# MDBU017A.net
KiCad netlist of a schematic drawn in Altium Designer
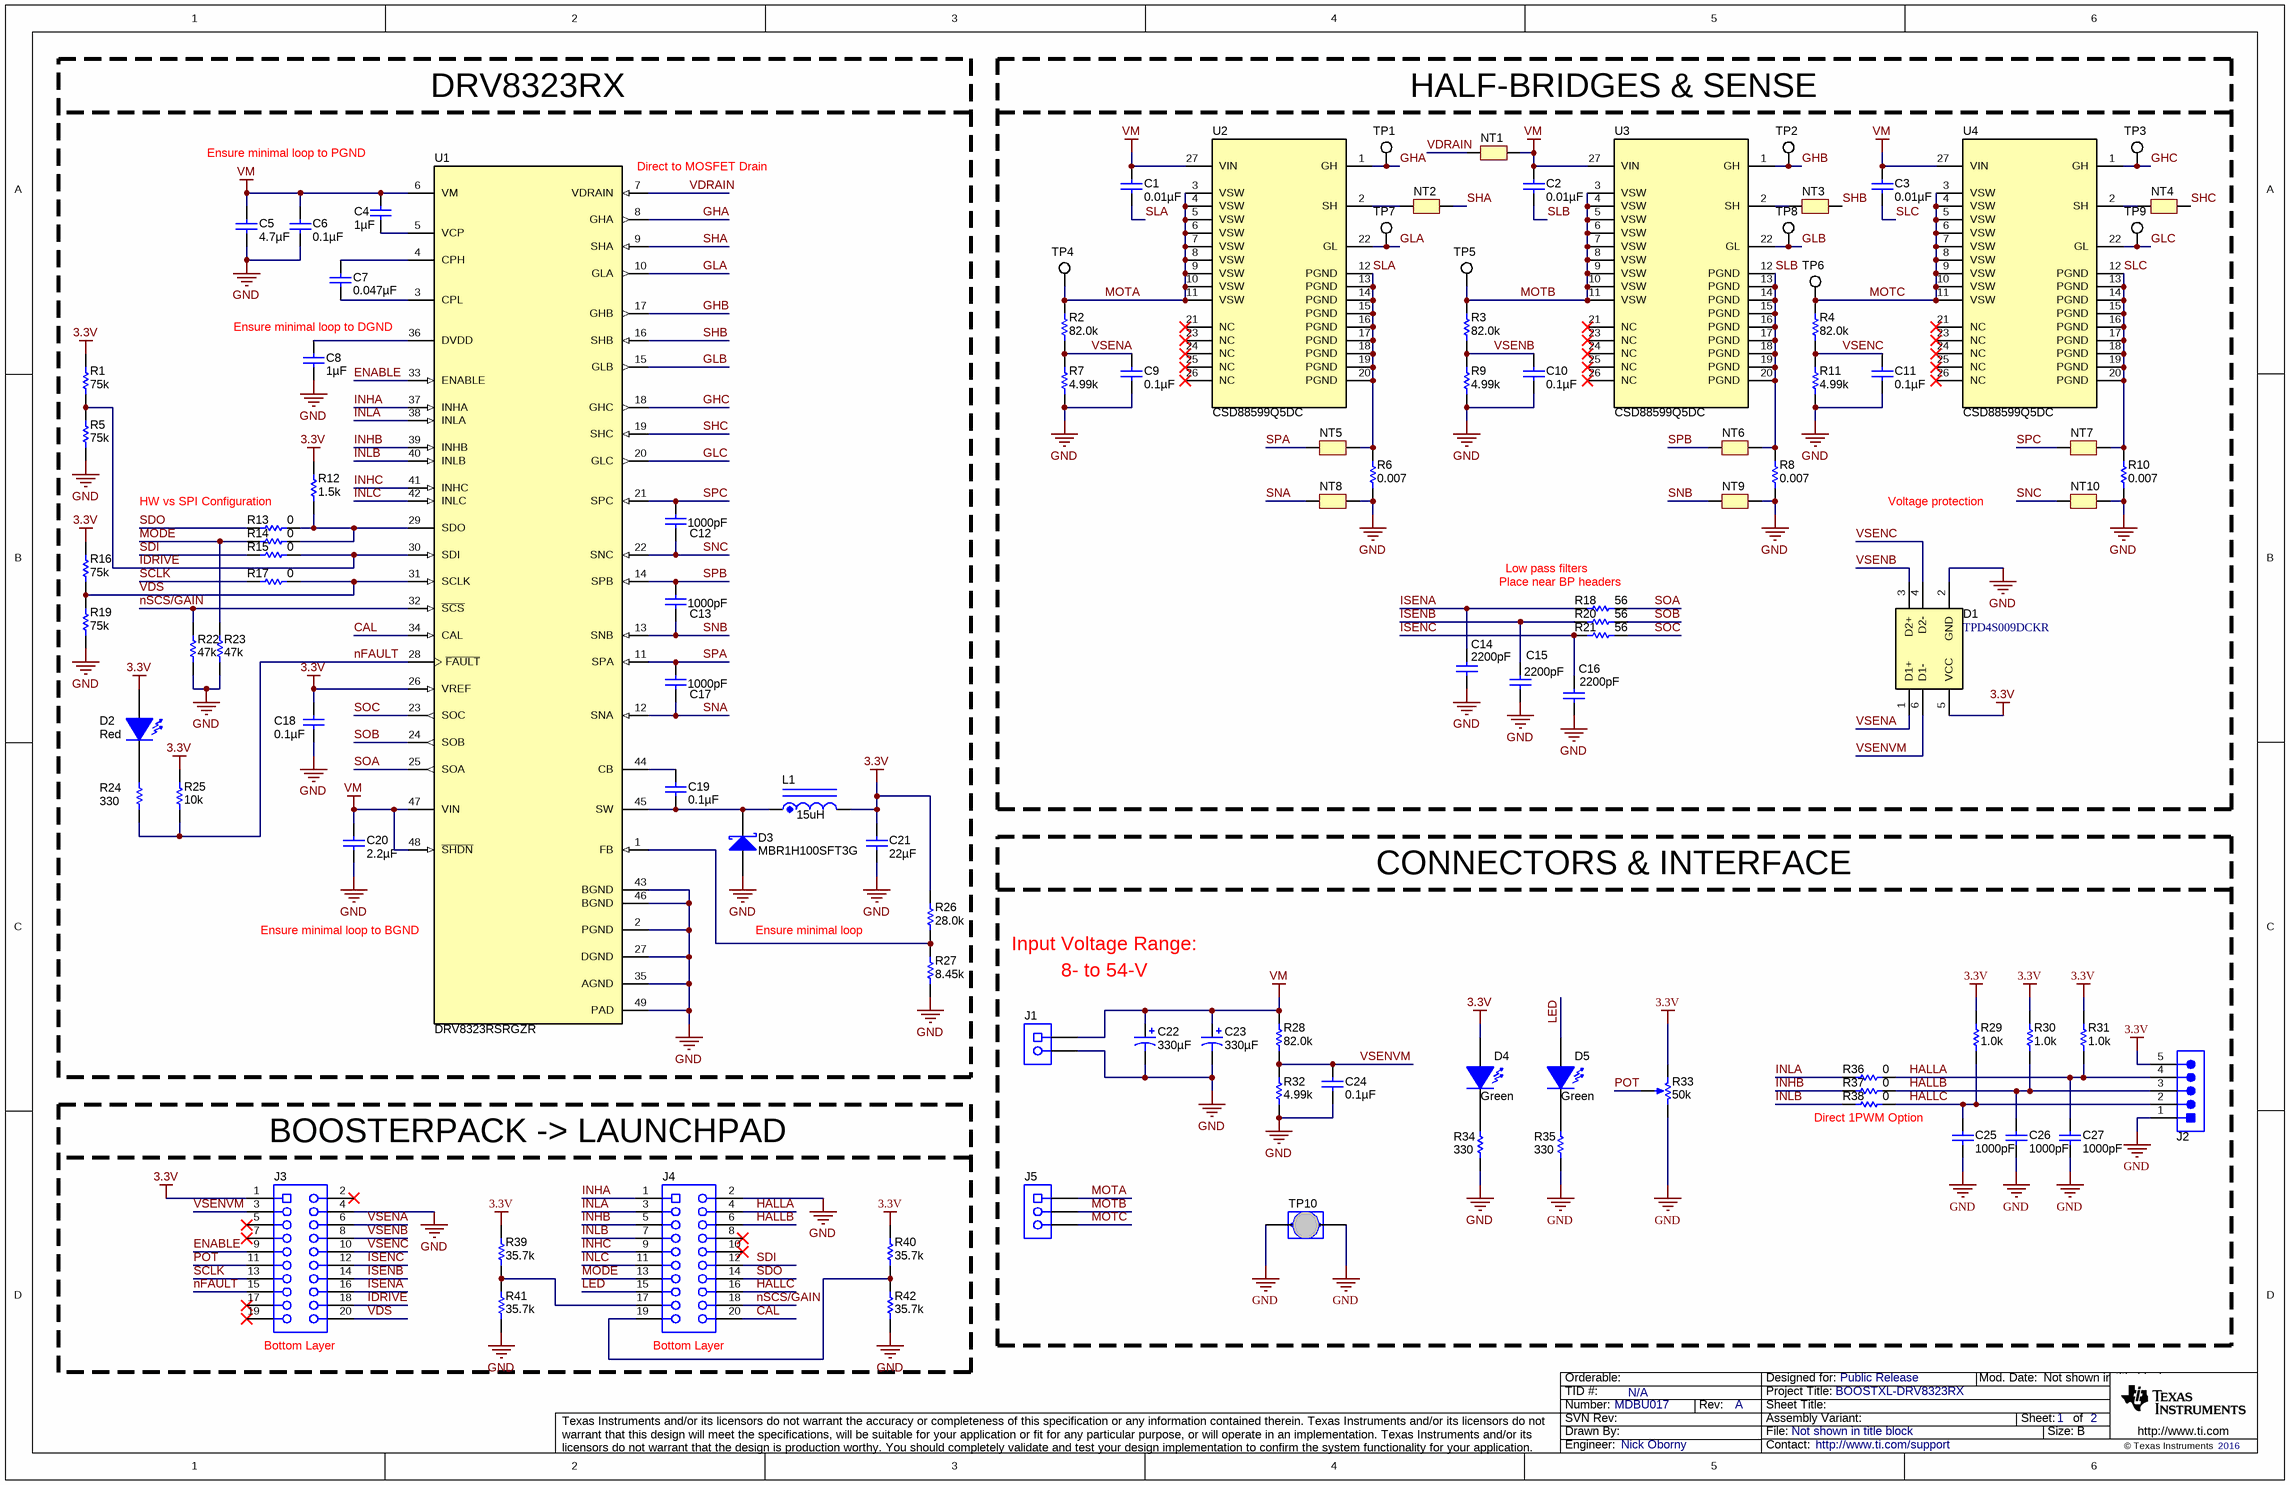
[diagram p0: MDBU017A.SchDoc]

(export (version "E")
  (design (tool "Eeschema 10.0.6"))
  (components
    (comp (ref "C1")
      (value "C0603C103K1RACTU")
      (footprint "0603L")
      (description "CAP, CERM, 0.01 µF, 100 V, +/- 10%, X7R, 0603")
      (fields
        (field (name "VALUEDISPLAYED") "0.01µF")
        (field (name "MANUFACTURER") "Kemet")
        (field (name "PUBLISHER") "Texas Instruments")
      )
      (libsource (lib "Capacitor_Ceramic") (part "C0603C103K1RACTU"))
    )
    (comp (ref "C2")
      (value "C0603C103K1RACTU")
      (footprint "0603L")
      (description "CAP, CERM, 0.01 µF, 100 V, +/- 10%, X7R, 0603")
      (fields
        (field (name "VALUEDISPLAYED") "0.01µF")
        (field (name "MANUFACTURER") "Kemet")
        (field (name "PUBLISHER") "Texas Instruments")
      )
      (libsource (lib "Capacitor_Ceramic") (part "C0603C103K1RACTU"))
    )
    (comp (ref "C3")
      (value "C0603C103K1RACTU")
      (footprint "0603L")
      (description "CAP, CERM, 0.01 µF, 100 V, +/- 10%, X7R, 0603")
      (fields
        (field (name "VALUEDISPLAYED") "0.01µF")
        (field (name "MANUFACTURER") "Kemet")
        (field (name "PUBLISHER") "Texas Instruments")
      )
      (libsource (lib "Capacitor_Ceramic") (part "C0603C103K1RACTU"))
    )
    (comp (ref "C4")
      (value "885012206052")
      (footprint "0603L")
      (description "CAP, CERM, 1 µF, 16 V, +/- 10%, X7R, 0603")
      (fields
        (field (name "VALUEDISPLAYED") "1µF")
        (field (name "MANUFACTURER") "Wurth Elektronik")
        (field (name "PUBLISHER") "Texas Instruments")
      )
      (libsource (lib "Capacitor_Ceramic") (part "885012206052"))
    )
    (comp (ref "C5")
      (value "GRM32ER71K475KE14L")
      (footprint "1210_270L")
      (description "CAP, CERM, 4.7 µF, 80 V, +/- 10%, X7R, 1210")
      (fields
        (field (name "VALUEDISPLAYED") "4.7µF")
        (field (name "MANUFACTURER") "MuRata")
        (field (name "PUBLISHER") "Texas Instruments")
      )
      (libsource (lib "Capacitor_Ceramic") (part "GRM32ER71K475KE14L"))
    )
    (comp (ref "C6")
      (value "GRM188R72A104KA35D")
      (footprint "0603L")
      (description "CAP, CERM, 0.1 µF, 100 V, +/- 10%, X7R, 0603")
      (fields
        (field (name "VALUEDISPLAYED") "0.1µF")
        (field (name "MANUFACTURER") "MuRata")
        (field (name "PUBLISHER") "Texas Instruments")
      )
      (libsource (lib "Capacitor_Ceramic") (part "GRM188R72A104KA35D"))
    )
    (comp (ref "C7")
      (value "C1608X7S2A473K080AB")
      (footprint "0603L")
      (description "CAP, CERM, 0.047 µF, 100 V, +/- 10%, X7S, 0603")
      (fields
        (field (name "VALUEDISPLAYED") "0.047µF")
        (field (name "MANUFACTURER") "TDK")
        (field (name "PUBLISHER") "Texas Instruments")
      )
      (libsource (lib "Capacitor_Ceramic") (part "C1608X7S2A473K080AB"))
    )
    (comp (ref "C8")
      (value "GRM188R70J105KA01D")
      (footprint "0603L")
      (description "CAP, CERM, 1 µF, 6.3 V, +/- 10%, X7R, 0603")
      (fields
        (field (name "VALUEDISPLAYED") "1µF")
        (field (name "MANUFACTURER") "MuRata")
        (field (name "PUBLISHER") "Texas Instruments")
      )
      (libsource (lib "Capacitor_Ceramic") (part "GRM188R70J105KA01D"))
    )
    (comp (ref "C9")
      (value "C0603C104J4RACTU")
      (footprint "0603L")
      (description "CAP, CERM, 0.1 µF, 16 V, +/- 5%, X7R, 0603")
      (fields
        (field (name "VALUEDISPLAYED") "0.1µF")
        (field (name "MANUFACTURER") "Kemet")
        (field (name "PUBLISHER") "Texas Instruments")
      )
      (libsource (lib "Capacitor_Ceramic") (part "C0603C104J4RACTU"))
    )
    (comp (ref "C10")
      (value "C0603C104J4RACTU")
      (footprint "0603L")
      (description "CAP, CERM, 0.1 µF, 16 V, +/- 5%, X7R, 0603")
      (fields
        (field (name "VALUEDISPLAYED") "0.1µF")
        (field (name "MANUFACTURER") "Kemet")
        (field (name "PUBLISHER") "Texas Instruments")
      )
      (libsource (lib "Capacitor_Ceramic") (part "C0603C104J4RACTU"))
    )
    (comp (ref "C11")
      (value "C0603C104J4RACTU")
      (footprint "0603L")
      (description "CAP, CERM, 0.1 µF, 16 V, +/- 5%, X7R, 0603")
      (fields
        (field (name "VALUEDISPLAYED") "0.1µF")
        (field (name "MANUFACTURER") "Kemet")
        (field (name "PUBLISHER") "Texas Instruments")
      )
      (libsource (lib "Capacitor_Ceramic") (part "C0603C104J4RACTU"))
    )
    (comp (ref "C12")
      (value "GRM188R71C102KA01D")
      (footprint "0603L")
      (description "CAP, CERM, 1000pF, 16V, +/-10%, X7R, 0603")
      (fields
        (field (name "VALUEDISPLAYED") "1000pF")
        (field (name "MANUFACTURER") "MuRata")
        (field (name "PUBLISHER") "Texas Instruments")
      )
      (libsource (lib "Capacitor_Ceramic") (part "GRM188R71C102KA01D"))
    )
    (comp (ref "C13")
      (value "GRM188R71C102KA01D")
      (footprint "0603L")
      (description "CAP, CERM, 1000pF, 16V, +/-10%, X7R, 0603")
      (fields
        (field (name "VALUEDISPLAYED") "1000pF")
        (field (name "MANUFACTURER") "MuRata")
        (field (name "PUBLISHER") "Texas Instruments")
      )
      (libsource (lib "Capacitor_Ceramic") (part "GRM188R71C102KA01D"))
    )
    (comp (ref "C14")
      (value "GRM188R71C222KA01D")
      (footprint "0603L")
      (description "CAP, CERM, 2200pF, 16V, +/-10%, X7R, 0603")
      (fields
        (field (name "VALUEDISPLAYED") "2200pF")
        (field (name "MANUFACTURER") "MuRata")
        (field (name "PUBLISHER") "Texas Instruments")
      )
      (libsource (lib "Capacitor_Ceramic") (part "GRM188R71C222KA01D"))
    )
    (comp (ref "C15")
      (value "GRM188R71C222KA01D")
      (footprint "0603L")
      (description "CAP, CERM, 2200pF, 16V, +/-10%, X7R, 0603")
      (fields
        (field (name "VALUEDISPLAYED") "2200pF")
        (field (name "MANUFACTURER") "MuRata")
        (field (name "PUBLISHER") "Texas Instruments")
      )
      (libsource (lib "Capacitor_Ceramic") (part "GRM188R71C222KA01D"))
    )
    (comp (ref "C16")
      (value "GRM188R71C222KA01D")
      (footprint "0603L")
      (description "CAP, CERM, 2200pF, 16V, +/-10%, X7R, 0603")
      (fields
        (field (name "VALUEDISPLAYED") "2200pF")
        (field (name "MANUFACTURER") "MuRata")
        (field (name "PUBLISHER") "Texas Instruments")
      )
      (libsource (lib "Capacitor_Ceramic") (part "GRM188R71C222KA01D"))
    )
    (comp (ref "C17")
      (value "GRM188R71C102KA01D")
      (footprint "0603L")
      (description "CAP, CERM, 1000pF, 16V, +/-10%, X7R, 0603")
      (fields
        (field (name "VALUEDISPLAYED") "1000pF")
        (field (name "MANUFACTURER") "MuRata")
        (field (name "PUBLISHER") "Texas Instruments")
      )
      (libsource (lib "Capacitor_Ceramic") (part "GRM188R71C102KA01D"))
    )
    (comp (ref "C18")
      (value "GRM188R70J104KA01D")
      (footprint "0603L")
      (description "CAP, CERM, 0.1 µF, 6.3 V, +/- 10%, X7R, 0603")
      (fields
        (field (name "VALUEDISPLAYED") "0.1µF")
        (field (name "MANUFACTURER") "MuRata")
        (field (name "PUBLISHER") "Texas Instruments")
      )
      (libsource (lib "Capacitor_Ceramic") (part "GRM188R70J104KA01D"))
    )
    (comp (ref "C19")
      (value "0603YC104JAT2A")
      (footprint "0603L")
      (description "CAP, CERM, 0.1 µF, 16 V, +/- 5%, X7R, 0603")
      (fields
        (field (name "VALUEDISPLAYED") "0.1µF")
        (field (name "MANUFACTURER") "AVX")
        (field (name "PUBLISHER") "Texas Instruments")
      )
      (libsource (lib "Capacitor_Ceramic") (part "0603YC104JAT2A"))
    )
    (comp (ref "C20")
      (value "HMK325B7225KN-T")
      (footprint "1210L")
      (description "CAP, CERM, 2.2 µF, 100 V, +/- 10%, X7R, 1210")
      (fields
        (field (name "VALUEDISPLAYED") "2.2µF")
        (field (name "MANUFACTURER") "Taiyo Yuden")
        (field (name "PUBLISHER") "Texas Instruments")
      )
      (libsource (lib "Capacitor_Ceramic") (part "HMK325B7225KN-T"))
    )
    (comp (ref "C21")
      (value "C3216X7S1A226M160AC")
      (footprint "1206_180L")
      (description "CAP, CERM, 22 µF, 10 V, +/- 20%, X7S, 1206")
      (fields
        (field (name "VALUEDISPLAYED") "22µF")
        (field (name "MANUFACTURER") "TDK")
        (field (name "PUBLISHER") "Texas Instruments")
      )
      (libsource (lib "Capacitor_Ceramic") (part "C3216X7S1A226M160AC"))
    )
    (comp (ref "C22")
      (value "EMVA630ADA331MKG5S")
      (footprint "CAPSMT_62_KG5")
      (description "CAP, AL, 330 µF, 63 V, +/- 20%, SMD")
      (fields
        (field (name "VALUEDISPLAYED") "330µF")
        (field (name "MANUFACTURER") "Chemi-Con")
        (field (name "PUBLISHER") "Texas Instruments")
      )
      (libsource (lib "Capacitor_Aluminum") (part "EMVA630ADA331MKG5S"))
    )
    (comp (ref "C23")
      (value "EMVA630ADA331MKG5S")
      (footprint "CAPSMT_62_KG5")
      (description "CAP, AL, 330 µF, 63 V, +/- 20%, SMD")
      (fields
        (field (name "VALUEDISPLAYED") "330µF")
        (field (name "MANUFACTURER") "Chemi-Con")
        (field (name "PUBLISHER") "Texas Instruments")
      )
      (libsource (lib "Capacitor_Aluminum") (part "EMVA630ADA331MKG5S"))
    )
    (comp (ref "C24")
      (value "C0603C104J4RACTU")
      (footprint "0603L")
      (description "CAP, CERM, 0.1 µF, 16 V, +/- 5%, X7R, 0603")
      (fields
        (field (name "VALUEDISPLAYED") "0.1µF")
        (field (name "MANUFACTURER") "Kemet")
        (field (name "PUBLISHER") "Texas Instruments")
      )
      (libsource (lib "Capacitor_Ceramic") (part "C0603C104J4RACTU"))
    )
    (comp (ref "C25")
      (value "885012206034")
      (footprint "0603L")
      (description "CAP, CERM, 1000 pF, 16 V, +/- 10%, X7R, 0603")
      (fields
        (field (name "VALUEDISPLAYED") "1000pF")
        (field (name "MANUFACTURER") "Wurth Elektronik")
        (field (name "PUBLISHER") "Texas Instruments")
      )
      (libsource (lib "Capacitor_Ceramic") (part "885012206034"))
    )
    (comp (ref "C26")
      (value "885012206034")
      (footprint "0603L")
      (description "CAP, CERM, 1000 pF, 16 V, +/- 10%, X7R, 0603")
      (fields
        (field (name "VALUEDISPLAYED") "1000pF")
        (field (name "MANUFACTURER") "Wurth Elektronik")
        (field (name "PUBLISHER") "Texas Instruments")
      )
      (libsource (lib "Capacitor_Ceramic") (part "885012206034"))
    )
    (comp (ref "C27")
      (value "885012206034")
      (footprint "0603L")
      (description "CAP, CERM, 1000 pF, 16 V, +/- 10%, X7R, 0603")
      (fields
        (field (name "VALUEDISPLAYED") "1000pF")
        (field (name "MANUFACTURER") "Wurth Elektronik")
        (field (name "PUBLISHER") "Texas Instruments")
      )
      (libsource (lib "Capacitor_Ceramic") (part "885012206034"))
    )
    (comp (ref "D1")
      (value "TPD4S009DCKR")
      (footprint "DCK0006A_L")
      (fields
        (field (name "MANUFACTURER") "Texas Instruments")
        (field (name "ALTERNATE PARTNUMBER") "Equivalent")
      )
      (libsource (lib "TI Interface ESD EMI Protection") (part "TPD4S009DCKR"))
    )
    (comp (ref "D2")
      (value "Red")
      (footprint "LED_LTST-C170")
      (description "LED, Red, SMD")
      (fields
        (field (name "MANUFACTURER") "Lite-On")
        (field (name "PARTNUMBER") "LTST-C170KRKT")
        (field (name "PUBLISHER") "Texas Instruments")
      )
      (libsource (lib "LED") (part "LTST-C170KRKT"))
    )
    (comp (ref "D3")
      (value "MBR1H100SFT3G")
      (footprint "SOD-123FL")
      (description "Diode, Schottky, 100 V, 1 A, SOD-123FL")
      (fields (field (name "MANUFACTURER") "ON Semiconductor") (field (name "PUBLISHER") "Texas Instruments"))
      (libsource (lib "Diode") (part "MBR1H100SFT3G"))
    )
    (comp (ref "D4")
      (value "Green")
      (footprint "LED_LTST-C171")
      (description "LED, Green, SMD")
      (fields
        (field (name "MANUFACTURER") "Lite-On")
        (field (name "PARTNUMBER") "LTST-C171GKT")
        (field (name "PUBLISHER") "Texas Instruments")
      )
      (libsource (lib "LED") (part "LTST-C171GKT"))
    )
    (comp (ref "D5")
      (value "Green")
      (footprint "LED_LTST-C171")
      (description "LED, Green, SMD")
      (fields
        (field (name "MANUFACTURER") "Lite-On")
        (field (name "PARTNUMBER") "LTST-C171GKT")
        (field (name "PUBLISHER") "Texas Instruments")
      )
      (libsource (lib "LED") (part "LTST-C171GKT"))
    )
    (comp (ref "J1")
      (value "691 101 710 002")
      (footprint "Wurth_691101710002")
      (description "Terminal Block, 5 mm, 2x1, Tin, TH")
      (fields
        (field (name "MANUFACTURER") "Wurth Elektronik eiSos")
        (field (name "SYMBOLCREATOR") "a0412235")
        (field (name "PUBLISHER") "Texas Instruments")
      )
      (libsource (lib "Connectors_Other") (part "691 101 710 002"))
    )
    (comp (ref "J2")
      (value "PEC05SAAN")
      (footprint "Sullins_PxC05SAAN")
      (description "Header, 2.54mm, 5x1, Tin, TH")
      (fields
        (field (name "MANUFACTURER") "Sullins Connector Solutions")
        (field (name "SYMBOLCREATOR") "a0412235")
        (field (name "PUBLISHER") "Texas Instruments")
      )
      (libsource (lib "Connectors_Sullins") (part "PEC05SAAN"))
    )
    (comp (ref "J3")
      (value "SSQ-110-03-G-D")
      (footprint "Samtec_SSQ-110-03-x-D")
      (description "Receptacle, 2.54mm, 10x2, Gold, TH")
      (fields
        (field (name "MANUFACTURER") "Samtec")
        (field (name "SYMBOLCREATOR") "a0412235")
        (field (name "PUBLISHER") "Texas Instruments")
      )
      (libsource (lib "Connectors_Samtec") (part "SSQ-110-03-G-D"))
    )
    (comp (ref "J4")
      (value "SSQ-110-03-G-D")
      (footprint "Samtec_SSQ-110-03-x-D")
      (description "Receptacle, 2.54mm, 10x2, Gold, TH")
      (fields
        (field (name "MANUFACTURER") "Samtec")
        (field (name "SYMBOLCREATOR") "a0412235")
        (field (name "PUBLISHER") "Texas Instruments")
      )
      (libsource (lib "Connectors_Samtec") (part "SSQ-110-03-G-D"))
    )
    (comp (ref "J5")
      (value "691 101 710 003")
      (footprint "Wurth_691101710003")
      (description "Terminal Block, 5 mm, 3x1, Tin, TH")
      (fields
        (field (name "MANUFACTURER") "Wurth Elektronik eiSos")
        (field (name "SYMBOLCREATOR") "a0412235")
        (field (name "PUBLISHER") "Texas Instruments")
      )
      (libsource (lib "Connectors_Other") (part "691 101 710 003"))
    )
    (comp (ref "L1")
      (value "15uH")
      (footprint "SD53")
      (description "Inductor, Shielded Drum Core, Ferrite, 15 µH, 1.1 A, 0.122 ohm, SMD")
      (fields
        (field (name "PARTNUMBER") "SD53-150-R")
        (field (name "MANUFACTURER") "Cooper Bussman")
        (field (name "SYMBOLCREATOR") "a0412235")
        (field (name "PUBLISHER") "Texas Instruments")
      )
      (libsource (lib "Inductor_Other") (part "SD53-150-R"))
    )
    (comp (ref "NT1")
      (value "Net-Tie")
      (footprint "Net-Tie_10mil")
      (description "Single point connection between nets.")
      (fields (field (name "SYMBOLCREATOR") "codlsc") (field (name "PUBLISHER") "Texas Instruments"))
      (libsource (lib "MiscParts") (part "Net-Tie"))
    )
    (comp (ref "NT2")
      (value "Net-Tie")
      (footprint "Net-Tie_10mil")
      (description "Single point connection between nets.")
      (fields (field (name "SYMBOLCREATOR") "codlsc") (field (name "PUBLISHER") "Texas Instruments"))
      (libsource (lib "MiscParts") (part "Net-Tie"))
    )
    (comp (ref "NT3")
      (value "Net-Tie")
      (footprint "Net-Tie_10mil")
      (description "Single point connection between nets.")
      (fields (field (name "SYMBOLCREATOR") "codlsc") (field (name "PUBLISHER") "Texas Instruments"))
      (libsource (lib "MiscParts") (part "Net-Tie"))
    )
    (comp (ref "NT4")
      (value "Net-Tie")
      (footprint "Net-Tie_10mil")
      (description "Single point connection between nets.")
      (fields (field (name "SYMBOLCREATOR") "codlsc") (field (name "PUBLISHER") "Texas Instruments"))
      (libsource (lib "MiscParts") (part "Net-Tie"))
    )
    (comp (ref "NT5")
      (value "Net-Tie")
      (footprint "Net-Tie_10mil")
      (description "Single point connection between nets.")
      (fields (field (name "SYMBOLCREATOR") "codlsc") (field (name "PUBLISHER") "Texas Instruments"))
      (libsource (lib "MiscParts") (part "Net-Tie"))
    )
    (comp (ref "NT6")
      (value "Net-Tie")
      (footprint "Net-Tie_10mil")
      (description "Single point connection between nets.")
      (fields (field (name "SYMBOLCREATOR") "codlsc") (field (name "PUBLISHER") "Texas Instruments"))
      (libsource (lib "MiscParts") (part "Net-Tie"))
    )
    (comp (ref "NT7")
      (value "Net-Tie")
      (footprint "Net-Tie_10mil")
      (description "Single point connection between nets.")
      (fields (field (name "SYMBOLCREATOR") "codlsc") (field (name "PUBLISHER") "Texas Instruments"))
      (libsource (lib "MiscParts") (part "Net-Tie"))
    )
    (comp (ref "NT8")
      (value "Net-Tie")
      (footprint "Net-Tie_10mil")
      (description "Single point connection between nets.")
      (fields (field (name "SYMBOLCREATOR") "codlsc") (field (name "PUBLISHER") "Texas Instruments"))
      (libsource (lib "MiscParts") (part "Net-Tie"))
    )
    (comp (ref "NT9")
      (value "Net-Tie")
      (footprint "Net-Tie_10mil")
      (description "Single point connection between nets.")
      (fields (field (name "SYMBOLCREATOR") "codlsc") (field (name "PUBLISHER") "Texas Instruments"))
      (libsource (lib "MiscParts") (part "Net-Tie"))
    )
    (comp (ref "NT10")
      (value "Net-Tie")
      (footprint "Net-Tie_10mil")
      (description "Single point connection between nets.")
      (fields (field (name "SYMBOLCREATOR") "codlsc") (field (name "PUBLISHER") "Texas Instruments"))
      (libsource (lib "MiscParts") (part "Net-Tie"))
    )
    (comp (ref "R1")
      (value "CRCW060375K0JNEA")
      (footprint "0603L")
      (description "RES, 75 k, 5%, 0.1 W, 0603")
      (fields
        (field (name "VALUEDISPLAYED") "75k")
        (field (name "MANUFACTURER") "Vishay-Dale")
        (field (name "PUBLISHER") "Texas Instruments")
      )
      (libsource (lib "Resistor_0603") (part "CRCW060375K0JNEA"))
    )
    (comp (ref "R2")
      (value "RC0603FR-0782KL")
      (footprint "0603L")
      (description "RES, 82.0 k, 1%, 0.1 W, 0603")
      (fields
        (field (name "VALUEDISPLAYED") "82.0k")
        (field (name "MANUFACTURER") "Yageo America")
        (field (name "PUBLISHER") "Texas Instruments")
      )
      (libsource (lib "Resistor_0603") (part "RC0603FR-0782KL"))
    )
    (comp (ref "R3")
      (value "RC0603FR-0782KL")
      (footprint "0603L")
      (description "RES, 82.0 k, 1%, 0.1 W, 0603")
      (fields
        (field (name "VALUEDISPLAYED") "82.0k")
        (field (name "MANUFACTURER") "Yageo America")
        (field (name "PUBLISHER") "Texas Instruments")
      )
      (libsource (lib "Resistor_0603") (part "RC0603FR-0782KL"))
    )
    (comp (ref "R4")
      (value "RC0603FR-0782KL")
      (footprint "0603L")
      (description "RES, 82.0 k, 1%, 0.1 W, 0603")
      (fields
        (field (name "VALUEDISPLAYED") "82.0k")
        (field (name "MANUFACTURER") "Yageo America")
        (field (name "PUBLISHER") "Texas Instruments")
      )
      (libsource (lib "Resistor_0603") (part "RC0603FR-0782KL"))
    )
    (comp (ref "R5")
      (value "CRCW060375K0JNEA")
      (footprint "0603L")
      (description "RES, 75 k, 5%, 0.1 W, 0603")
      (fields
        (field (name "VALUEDISPLAYED") "75k")
        (field (name "MANUFACTURER") "Vishay-Dale")
        (field (name "PUBLISHER") "Texas Instruments")
      )
      (libsource (lib "Resistor_0603") (part "CRCW060375K0JNEA"))
    )
    (comp (ref "R6")
      (value "CRE2512-FZ-R007E-3")
      (footprint "2512L")
      (description "RES SMD 0.007 OHM 1% 3W 2512")
      (fields
        (field (name "VALUEDISPLAYED") "0.007")
        (field (name "MANUFACTURER") "Bourns Inc.")
        (field (name "PUBLISHER") "Texas Instruments")
      )
      (libsource (lib "Resistor_2512") (part "PMR100HZPFU7L00"))
    )
    (comp (ref "R7")
      (value "RC0603FR-074K99L")
      (footprint "0603L")
      (description "RES, 4.99 k, 1%, 0.1 W, 0603")
      (fields
        (field (name "VALUEDISPLAYED") "4.99k")
        (field (name "MANUFACTURER") "Yageo America")
        (field (name "PUBLISHER") "Texas Instruments")
      )
      (libsource (lib "Resistor_0603") (part "RC0603FR-074K99L"))
    )
    (comp (ref "R8")
      (value "CRE2512-FZ-R007E-3")
      (footprint "2512L")
      (description "RES SMD 0.007 OHM 1% 3W 2512")
      (fields
        (field (name "VALUEDISPLAYED") "0.007")
        (field (name "MANUFACTURER") "Bourns Inc.")
        (field (name "PUBLISHER") "Texas Instruments")
      )
      (libsource (lib "Resistor_2512") (part "PMR100HZPFU7L00"))
    )
    (comp (ref "R9")
      (value "RC0603FR-074K99L")
      (footprint "0603L")
      (description "RES, 4.99 k, 1%, 0.1 W, 0603")
      (fields
        (field (name "VALUEDISPLAYED") "4.99k")
        (field (name "MANUFACTURER") "Yageo America")
        (field (name "PUBLISHER") "Texas Instruments")
      )
      (libsource (lib "Resistor_0603") (part "RC0603FR-074K99L"))
    )
    (comp (ref "R10")
      (value "CRE2512-FZ-R007E-3")
      (footprint "2512L")
      (description "RES SMD 0.007 OHM 1% 3W 2512")
      (fields
        (field (name "VALUEDISPLAYED") "0.007")
        (field (name "MANUFACTURER") "Bourns Inc.")
        (field (name "PUBLISHER") "Texas Instruments")
      )
      (libsource (lib "Resistor_2512") (part "PMR100HZPFU7L00"))
    )
    (comp (ref "R11")
      (value "RC0603FR-074K99L")
      (footprint "0603L")
      (description "RES, 4.99 k, 1%, 0.1 W, 0603")
      (fields
        (field (name "VALUEDISPLAYED") "4.99k")
        (field (name "MANUFACTURER") "Yageo America")
        (field (name "PUBLISHER") "Texas Instruments")
      )
      (libsource (lib "Resistor_0603") (part "RC0603FR-074K99L"))
    )
    (comp (ref "R12")
      (value "CRCW06031K50JNEA")
      (footprint "0603L")
      (description "RES, 1.5 k, 5%, 0.1 W, 0603")
      (fields
        (field (name "VALUEDISPLAYED") "1.5k")
        (field (name "MANUFACTURER") "Vishay-Dale")
        (field (name "PUBLISHER") "Texas Instruments")
      )
      (libsource (lib "Resistor_0603") (part "CRCW06031K50JNEA"))
    )
    (comp (ref "R13")
      (value "0")
      (footprint "0603L")
      (description "RES, 0, 5%, 0.1 W, 0603")
      (fields
        (field (name "PARTNUMBER") "CRCW06030000Z0EA")
        (field (name "MANUFACTURER") "Vishay-Dale")
        (field (name "PUBLISHER") "Texas Instruments")
      )
      (libsource (lib "Resistor_0603") (part "CRCW06030000Z0EA"))
    )
    (comp (ref "R14")
      (value "0")
      (footprint "0603L")
      (description "RES, 0, 5%, 0.1 W, 0603")
      (fields
        (field (name "PARTNUMBER") "CRCW06030000Z0EA")
        (field (name "MANUFACTURER") "Vishay-Dale")
        (field (name "PUBLISHER") "Texas Instruments")
      )
      (libsource (lib "Resistor_0603") (part "CRCW06030000Z0EA"))
    )
    (comp (ref "R15")
      (value "0")
      (footprint "0603L")
      (description "RES, 0, 5%, 0.1 W, 0603")
      (fields
        (field (name "PARTNUMBER") "CRCW06030000Z0EA")
        (field (name "MANUFACTURER") "Vishay-Dale")
        (field (name "PUBLISHER") "Texas Instruments")
      )
      (libsource (lib "Resistor_0603") (part "CRCW06030000Z0EA"))
    )
    (comp (ref "R16")
      (value "CRCW060375K0JNEA")
      (footprint "0603L")
      (description "RES, 75 k, 5%, 0.1 W, 0603")
      (fields
        (field (name "VALUEDISPLAYED") "75k")
        (field (name "MANUFACTURER") "Vishay-Dale")
        (field (name "PUBLISHER") "Texas Instruments")
      )
      (libsource (lib "Resistor_0603") (part "CRCW060375K0JNEA"))
    )
    (comp (ref "R17")
      (value "0")
      (footprint "0603L")
      (description "RES, 0, 5%, 0.1 W, 0603")
      (fields
        (field (name "PARTNUMBER") "CRCW06030000Z0EA")
        (field (name "MANUFACTURER") "Vishay-Dale")
        (field (name "PUBLISHER") "Texas Instruments")
      )
      (libsource (lib "Resistor_0603") (part "CRCW06030000Z0EA"))
    )
    (comp (ref "R18")
      (value "56")
      (footprint "0603L")
      (description "RES, 56 ohm, 5%, 0.1W, 0603")
      (fields
        (field (name "PARTNUMBER") "CRCW060356R0JNEA")
        (field (name "MANUFACTURER") "Vishay-Dale")
        (field (name "PUBLISHER") "Texas Instruments")
      )
      (libsource (lib "Resistor_0603") (part "CRCW060356R0JNEA"))
    )
    (comp (ref "R19")
      (value "CRCW060375K0JNEA")
      (footprint "0603L")
      (description "RES, 75 k, 5%, 0.1 W, 0603")
      (fields
        (field (name "VALUEDISPLAYED") "75k")
        (field (name "MANUFACTURER") "Vishay-Dale")
        (field (name "PUBLISHER") "Texas Instruments")
      )
      (libsource (lib "Resistor_0603") (part "CRCW060375K0JNEA"))
    )
    (comp (ref "R20")
      (value "56")
      (footprint "0603L")
      (description "RES, 56 ohm, 5%, 0.1W, 0603")
      (fields
        (field (name "PARTNUMBER") "CRCW060356R0JNEA")
        (field (name "MANUFACTURER") "Vishay-Dale")
        (field (name "PUBLISHER") "Texas Instruments")
      )
      (libsource (lib "Resistor_0603") (part "CRCW060356R0JNEA"))
    )
    (comp (ref "R21")
      (value "56")
      (footprint "0603L")
      (description "RES, 56 ohm, 5%, 0.1W, 0603")
      (fields
        (field (name "PARTNUMBER") "CRCW060356R0JNEA")
        (field (name "MANUFACTURER") "Vishay-Dale")
        (field (name "PUBLISHER") "Texas Instruments")
      )
      (libsource (lib "Resistor_0603") (part "CRCW060356R0JNEA"))
    )
    (comp (ref "R22")
      (value "CRCW060347K0JNEA")
      (footprint "0603L")
      (description "RES, 47 k, 5%, 0.1 W, 0603")
      (fields
        (field (name "VALUEDISPLAYED") "47k")
        (field (name "MANUFACTURER") "Vishay-Dale")
        (field (name "PUBLISHER") "Texas Instruments")
      )
      (libsource (lib "Resistor_0603") (part "CRCW060347K0JNEA"))
    )
    (comp (ref "R23")
      (value "CRCW060347K0JNEA")
      (footprint "0603L")
      (description "RES, 47 k, 5%, 0.1 W, 0603")
      (fields
        (field (name "VALUEDISPLAYED") "47k")
        (field (name "MANUFACTURER") "Vishay-Dale")
        (field (name "PUBLISHER") "Texas Instruments")
      )
      (libsource (lib "Resistor_0603") (part "CRCW060347K0JNEA"))
    )
    (comp (ref "R24")
      (value "330")
      (footprint "0603L")
      (description "RES, 330 ohm, 5%, 0.1W, 0603")
      (fields
        (field (name "PARTNUMBER") "CRCW0603330RJNEA")
        (field (name "MANUFACTURER") "Vishay-Dale")
        (field (name "PUBLISHER") "Texas Instruments")
      )
      (libsource (lib "Resistor_0603") (part "CRCW0603330RJNEA"))
    )
    (comp (ref "R25")
      (value "CRCW060310K0JNEA")
      (footprint "0603L")
      (description "RES, 10 k, 5%, 0.1 W, 0603")
      (fields
        (field (name "VALUEDISPLAYED") "10k")
        (field (name "MANUFACTURER") "Vishay-Dale")
        (field (name "PUBLISHER") "Texas Instruments")
      )
      (libsource (lib "Resistor_0603") (part "CRCW060310K0JNEA"))
    )
    (comp (ref "R26")
      (value "CRCW060328K0FKEA")
      (footprint "0603L")
      (description "RES, 28.0 k, 1%, 0.1 W, 0603")
      (fields
        (field (name "VALUEDISPLAYED") "28.0k")
        (field (name "MANUFACTURER") "Vishay-Dale")
        (field (name "PUBLISHER") "Texas Instruments")
      )
      (libsource (lib "Resistor_0603") (part "CRCW060328K0FKEA"))
    )
    (comp (ref "R27")
      (value "CRCW06038K45FKEA")
      (footprint "0603L")
      (description "RES, 8.45 k, 1%, 0.1 W, 0603")
      (fields
        (field (name "VALUEDISPLAYED") "8.45k")
        (field (name "MANUFACTURER") "Vishay-Dale")
        (field (name "PUBLISHER") "Texas Instruments")
      )
      (libsource (lib "Resistor_0603") (part "CRCW06038K45FKEA"))
    )
    (comp (ref "R28")
      (value "RC0603FR-0782KL")
      (footprint "0603L")
      (description "RES, 82.0 k, 1%, 0.1 W, 0603")
      (fields
        (field (name "VALUEDISPLAYED") "82.0k")
        (field (name "MANUFACTURER") "Yageo America")
        (field (name "PUBLISHER") "Texas Instruments")
      )
      (libsource (lib "Resistor_0603") (part "RC0603FR-0782KL"))
    )
    (comp (ref "R29")
      (value "CRCW06031K00JNEA")
      (footprint "0603L")
      (description "RES, 1.0 k, 5%, 0.1 W, 0603")
      (fields
        (field (name "VALUEDISPLAYED") "1.0k")
        (field (name "MANUFACTURER") "Vishay-Dale")
        (field (name "PUBLISHER") "Texas Instruments")
      )
      (libsource (lib "Resistor_0603") (part "CRCW06031K00JNEA"))
    )
    (comp (ref "R30")
      (value "CRCW06031K00JNEA")
      (footprint "0603L")
      (description "RES, 1.0 k, 5%, 0.1 W, 0603")
      (fields
        (field (name "VALUEDISPLAYED") "1.0k")
        (field (name "MANUFACTURER") "Vishay-Dale")
        (field (name "PUBLISHER") "Texas Instruments")
      )
      (libsource (lib "Resistor_0603") (part "CRCW06031K00JNEA"))
    )
    (comp (ref "R31")
      (value "CRCW06031K00JNEA")
      (footprint "0603L")
      (description "RES, 1.0 k, 5%, 0.1 W, 0603")
      (fields
        (field (name "VALUEDISPLAYED") "1.0k")
        (field (name "MANUFACTURER") "Vishay-Dale")
        (field (name "PUBLISHER") "Texas Instruments")
      )
      (libsource (lib "Resistor_0603") (part "CRCW06031K00JNEA"))
    )
    (comp (ref "R32")
      (value "RC0603FR-074K99L")
      (footprint "0603L")
      (description "RES, 4.99 k, 1%, 0.1 W, 0603")
      (fields
        (field (name "VALUEDISPLAYED") "4.99k")
        (field (name "MANUFACTURER") "Yageo America")
        (field (name "PUBLISHER") "Texas Instruments")
      )
      (libsource (lib "Resistor_0603") (part "RC0603FR-074K99L"))
    )
    (comp (ref "R33")
      (value "50k")
      (footprint "Bourns_3352T")
      (description "Trimming Potentiometer, 50K, 0.5W, TH")
      (fields
        (field (name "PARTNUMBER") "3352T-1-503LF")
        (field (name "MANUFACTURER") "Bourns")
        (field (name "SYMBOLCREATOR") "a0412235")
        (field (name "PUBLISHER") "Texas Instruments")
      )
      (libsource (lib "Other_Passive") (part "3352T-1-503LF"))
    )
    (comp (ref "R34")
      (value "330")
      (footprint "0603L")
      (description "RES, 330 ohm, 5%, 0.1W, 0603")
      (fields
        (field (name "PARTNUMBER") "CRCW0603330RJNEA")
        (field (name "MANUFACTURER") "Vishay-Dale")
        (field (name "PUBLISHER") "Texas Instruments")
      )
      (libsource (lib "Resistor_0603") (part "CRCW0603330RJNEA"))
    )
    (comp (ref "R35")
      (value "330")
      (footprint "0603L")
      (description "RES, 330, 5%, 0.1 W, 0603")
      (fields
        (field (name "PARTNUMBER") "CRCW0603330RJNEA")
        (field (name "MANUFACTURER") "Vishay-Dale")
        (field (name "PUBLISHER") "Texas Instruments")
      )
      (libsource (lib "Resistor_0603") (part "CRCW0603330RJNEA"))
    )
    (comp (ref "R36")
      (value "0")
      (footprint "0603L")
      (description "RES, 0, 5%, 0.1 W, 0603")
      (fields
        (field (name "PARTNUMBER") "CRCW06030000Z0EA")
        (field (name "MANUFACTURER") "Vishay-Dale")
        (field (name "PUBLISHER") "Texas Instruments")
      )
      (libsource (lib "Resistor_0603") (part "CRCW06030000Z0EA"))
    )
    (comp (ref "R37")
      (value "0")
      (footprint "0603L")
      (description "RES, 0, 5%, 0.1 W, 0603")
      (fields
        (field (name "PARTNUMBER") "CRCW06030000Z0EA")
        (field (name "MANUFACTURER") "Vishay-Dale")
        (field (name "PUBLISHER") "Texas Instruments")
      )
      (libsource (lib "Resistor_0603") (part "CRCW06030000Z0EA"))
    )
    (comp (ref "R38")
      (value "0")
      (footprint "0603L")
      (description "RES, 0, 5%, 0.1 W, 0603")
      (fields
        (field (name "PARTNUMBER") "CRCW06030000Z0EA")
        (field (name "MANUFACTURER") "Vishay-Dale")
        (field (name "PUBLISHER") "Texas Instruments")
      )
      (libsource (lib "Resistor_0603") (part "CRCW06030000Z0EA"))
    )
    (comp (ref "R39")
      (value "RC0603FR-0735K7L")
      (footprint "0603L")
      (description "RES, 35.7 k, 1%, 0.1 W, 0603")
      (fields
        (field (name "VALUEDISPLAYED") "35.7k")
        (field (name "MANUFACTURER") "Yageo America")
        (field (name "PUBLISHER") "Texas Instruments")
      )
      (libsource (lib "Resistor_0603") (part "RC0603FR-0735K7L"))
    )
    (comp (ref "R40")
      (value "RC0603FR-0735K7L")
      (footprint "0603L")
      (description "RES, 35.7 k, 1%, 0.1 W, 0603")
      (fields
        (field (name "VALUEDISPLAYED") "35.7k")
        (field (name "MANUFACTURER") "Yageo America")
        (field (name "PUBLISHER") "Texas Instruments")
      )
      (libsource (lib "Resistor_0603") (part "RC0603FR-0735K7L"))
    )
    (comp (ref "R41")
      (value "RC0603FR-0735K7L")
      (footprint "0603L")
      (description "RES, 35.7 k, 1%, 0.1 W, 0603")
      (fields
        (field (name "VALUEDISPLAYED") "35.7k")
        (field (name "MANUFACTURER") "Yageo America")
        (field (name "PUBLISHER") "Texas Instruments")
      )
      (libsource (lib "Resistor_0603") (part "RC0603FR-0735K7L"))
    )
    (comp (ref "R42")
      (value "RC0603FR-0735K7L")
      (footprint "0603L")
      (description "RES, 35.7 k, 1%, 0.1 W, 0603")
      (fields
        (field (name "VALUEDISPLAYED") "35.7k")
        (field (name "MANUFACTURER") "Yageo America")
        (field (name "PUBLISHER") "Texas Instruments")
      )
      (libsource (lib "Resistor_0603") (part "RC0603FR-0735K7L"))
    )
    (comp (ref "TP1")
      (value "5002")
      (footprint "Keystone5002")
      (description "Test Point, Miniature, White, TH")
      (fields (field (name "MANUFACTURER") "Keystone") (field (name "PUBLISHER") "Texas Instruments"))
      (libsource (lib "Connectors_Keystone") (part "5002"))
    )
    (comp (ref "TP2")
      (value "5002")
      (footprint "Keystone5002")
      (description "Test Point, Miniature, White, TH")
      (fields (field (name "MANUFACTURER") "Keystone") (field (name "PUBLISHER") "Texas Instruments"))
      (libsource (lib "Connectors_Keystone") (part "5002"))
    )
    (comp (ref "TP3")
      (value "5002")
      (footprint "Keystone5002")
      (description "Test Point, Miniature, White, TH")
      (fields (field (name "MANUFACTURER") "Keystone") (field (name "PUBLISHER") "Texas Instruments"))
      (libsource (lib "Connectors_Keystone") (part "5002"))
    )
    (comp (ref "TP4")
      (value "5002")
      (footprint "Keystone5002")
      (description "Test Point, Miniature, White, TH")
      (fields (field (name "MANUFACTURER") "Keystone") (field (name "PUBLISHER") "Texas Instruments"))
      (libsource (lib "Connectors_Keystone") (part "5002"))
    )
    (comp (ref "TP5")
      (value "5002")
      (footprint "Keystone5002")
      (description "Test Point, Miniature, White, TH")
      (fields (field (name "MANUFACTURER") "Keystone") (field (name "PUBLISHER") "Texas Instruments"))
      (libsource (lib "Connectors_Keystone") (part "5002"))
    )
    (comp (ref "TP6")
      (value "5002")
      (footprint "Keystone5002")
      (description "Test Point, Miniature, White, TH")
      (fields (field (name "MANUFACTURER") "Keystone") (field (name "PUBLISHER") "Texas Instruments"))
      (libsource (lib "Connectors_Keystone") (part "5002"))
    )
    (comp (ref "TP7")
      (value "5002")
      (footprint "Keystone5002")
      (description "Test Point, Miniature, White, TH")
      (fields (field (name "MANUFACTURER") "Keystone") (field (name "PUBLISHER") "Texas Instruments"))
      (libsource (lib "Connectors_Keystone") (part "5002"))
    )
    (comp (ref "TP8")
      (value "5002")
      (footprint "Keystone5002")
      (description "Test Point, Miniature, White, TH")
      (fields (field (name "MANUFACTURER") "Keystone") (field (name "PUBLISHER") "Texas Instruments"))
      (libsource (lib "Connectors_Keystone") (part "5002"))
    )
    (comp (ref "TP9")
      (value "5002")
      (footprint "Keystone5002")
      (description "Test Point, Miniature, White, TH")
      (fields (field (name "MANUFACTURER") "Keystone") (field (name "PUBLISHER") "Texas Instruments"))
      (libsource (lib "Connectors_Keystone") (part "5002"))
    )
    (comp (ref "TP10")
      (value "D3082-05")
      (footprint "Harwin_D3082-05")
      (description "1mm Uninsulated Shorting Plug, 10.16mm spacing, TH")
      (fields
        (field (name "MANUFACTURER") "Harwin")
        (field (name "SYMBOLCREATOR") "a0799628")
        (field (name "PUBLISHER") "Texas Instruments")
      )
      (libsource (lib "Connectors_Other") (part "D3082-05"))
    )
    (comp (ref "U1")
      (value "DRV8323RSRGZR")
      (footprint "RGZ0048B")
      (description "60-V Three-Phase Smart Gate Driver, RGZ0048B")
      (fields
        (field (name "ALTERNATE PARTNUMBER") "DRV8323RSRGZT")
        (field (name "MANUFACTURER") "Texas Instruments")
        (field (name "SYMBOLCREATOR") "Altium")
        (field (name "PUBLISHER") "Texas Instruments")
      )
      (libsource (lib "TI_Pre_RTM") (part "DRV8323RSRGZR"))
    )
    (comp (ref "U2")
      (value "CSD88599Q5DC")
      (footprint "DMM0022A")
      (description "60 V Half-Bridge NexFE Power Block, DMM0022A (LSON-CLIP-27)")
      (fields
        (field (name "ALTERNATE PARTNUMBER") "CSD88599Q5DCT")
        (field (name "MANUFACTURER") "Texas Instruments")
        (field (name "SYMBOLCREATOR") "Altium")
        (field (name "PUBLISHER") "Texas Instruments")
      )
      (libsource (lib "TI_Pre_RTM") (part "CSD88599Q5DC"))
    )
    (comp (ref "U3")
      (value "CSD88599Q5DC")
      (footprint "DMM0022A")
      (description "60 V Half-Bridge NexFE Power Block, DMM0022A (LSON-CLIP-27)")
      (fields
        (field (name "ALTERNATE PARTNUMBER") "CSD88599Q5DCT")
        (field (name "MANUFACTURER") "Texas Instruments")
        (field (name "SYMBOLCREATOR") "Altium")
        (field (name "PUBLISHER") "Texas Instruments")
      )
      (libsource (lib "TI_Pre_RTM") (part "CSD88599Q5DC"))
    )
    (comp (ref "U4")
      (value "CSD88599Q5DC")
      (footprint "DMM0022A")
      (description "60 V Half-Bridge NexFE Power Block, DMM0022A (LSON-CLIP-27)")
      (fields
        (field (name "ALTERNATE PARTNUMBER") "CSD88599Q5DCT")
        (field (name "MANUFACTURER") "Texas Instruments")
        (field (name "SYMBOLCREATOR") "Altium")
        (field (name "PUBLISHER") "Texas Instruments")
      )
      (libsource (lib "TI_Pre_RTM") (part "CSD88599Q5DC"))
    )
  )
  (nets
    (net (code "1") (name "/CAL") (class "Default")
      (node (ref "J4") (pin "20") (pinfunction "20_20") (pintype "passive"))
      (node (ref "U1") (pin "34") (pinfunction "CAL_34") (pintype "input"))
    )
    (net (code "2") (name "/ENABLE") (class "Default")
      (node (ref "J3") (pin "9") (pinfunction "9_9") (pintype "passive"))
      (node (ref "U1") (pin "33") (pinfunction "ENABLE_33") (pintype "input"))
    )
    (net (code "3") (name "/GHA") (class "Default")
      (node (ref "TP1") (pin "1") (pintype "passive"))
      (node (ref "U1") (pin "8") (pinfunction "GHA_8") (pintype "output"))
      (node (ref "U2") (pin "1") (pinfunction "GH_1") (pintype "passive"))
    )
    (net (code "4") (name "/GHB") (class "Default")
      (node (ref "TP2") (pin "1") (pintype "passive"))
      (node (ref "U1") (pin "17") (pinfunction "GHB_17") (pintype "output"))
      (node (ref "U3") (pin "1") (pinfunction "GH_1") (pintype "passive"))
    )
    (net (code "5") (name "/GHC") (class "Default")
      (node (ref "TP3") (pin "1") (pintype "passive"))
      (node (ref "U1") (pin "18") (pinfunction "GHC_18") (pintype "output"))
      (node (ref "U4") (pin "1") (pinfunction "GH_1") (pintype "passive"))
    )
    (net (code "6") (name "/GLA") (class "Default")
      (node (ref "TP7") (pin "1") (pintype "passive"))
      (node (ref "U1") (pin "10") (pinfunction "GLA_10") (pintype "output"))
      (node (ref "U2") (pin "22") (pinfunction "GL_22") (pintype "passive"))
    )
    (net (code "7") (name "/GLB") (class "Default")
      (node (ref "TP8") (pin "1") (pintype "passive"))
      (node (ref "U1") (pin "15") (pinfunction "GLB_15") (pintype "output"))
      (node (ref "U3") (pin "22") (pinfunction "GL_22") (pintype "passive"))
    )
    (net (code "8") (name "/GLC") (class "Default")
      (node (ref "TP9") (pin "1") (pintype "passive"))
      (node (ref "U1") (pin "20") (pinfunction "GLC_20") (pintype "output"))
      (node (ref "U4") (pin "22") (pinfunction "GL_22") (pintype "passive"))
    )
    (net (code "9") (name "/HALLA") (class "Default")
      (node (ref "C27") (pin "1") (pinfunction "1_1") (pintype "passive"))
      (node (ref "J2") (pin "4") (pinfunction "4_4") (pintype "passive"))
      (node (ref "J4") (pin "4") (pinfunction "4_4") (pintype "passive"))
      (node (ref "R31") (pin "1") (pinfunction "1_1") (pintype "passive"))
      (node (ref "R36") (pin "1") (pinfunction "1_1") (pintype "passive"))
    )
    (net (code "10") (name "/HALLB") (class "Default")
      (node (ref "C26") (pin "1") (pinfunction "1_1") (pintype "passive"))
      (node (ref "J2") (pin "3") (pinfunction "3_3") (pintype "passive"))
      (node (ref "J4") (pin "6") (pinfunction "6_6") (pintype "passive"))
      (node (ref "R30") (pin "1") (pinfunction "1_1") (pintype "passive"))
      (node (ref "R37") (pin "1") (pinfunction "1_1") (pintype "passive"))
    )
    (net (code "11") (name "/HALLC") (class "Default")
      (node (ref "C25") (pin "1") (pinfunction "1_1") (pintype "passive"))
      (node (ref "J2") (pin "2") (pinfunction "2_2") (pintype "passive"))
      (node (ref "J4") (pin "16") (pinfunction "16_16") (pintype "passive"))
      (node (ref "R29") (pin "1") (pinfunction "1_1") (pintype "passive"))
      (node (ref "R38") (pin "1") (pinfunction "1_1") (pintype "passive"))
    )
    (net (code "12") (name "/IDRIVE") (class "Default")
      (node (ref "J3") (pin "18") (pinfunction "18_18") (pintype "passive"))
      (node (ref "R1") (pin "1") (pinfunction "1_1") (pintype "passive"))
      (node (ref "R15") (pin "1") (pinfunction "1_1") (pintype "passive"))
      (node (ref "R5") (pin "2") (pinfunction "2_2") (pintype "passive"))
      (node (ref "U1") (pin "30") (pinfunction "SDI_30") (pintype "input"))
    )
    (net (code "13") (name "/INHA") (class "Default")
      (node (ref "J4") (pin "1") (pinfunction "1_1") (pintype "passive"))
      (node (ref "U1") (pin "37") (pinfunction "INHA_37") (pintype "input"))
    )
    (net (code "14") (name "/INHB") (class "Default")
      (node (ref "J4") (pin "5") (pinfunction "5_5") (pintype "passive"))
      (node (ref "R37") (pin "2") (pinfunction "2_2") (pintype "passive"))
      (node (ref "U1") (pin "39") (pinfunction "INHB_39") (pintype "input"))
    )
    (net (code "15") (name "/INHC") (class "Default")
      (node (ref "J4") (pin "9") (pinfunction "9_9") (pintype "passive"))
      (node (ref "U1") (pin "41") (pinfunction "INHC_41") (pintype "input"))
    )
    (net (code "16") (name "/INLA") (class "Default")
      (node (ref "J4") (pin "3") (pinfunction "3_3") (pintype "passive"))
      (node (ref "R36") (pin "2") (pinfunction "2_2") (pintype "passive"))
      (node (ref "U1") (pin "38") (pinfunction "INLA_38") (pintype "input"))
    )
    (net (code "17") (name "/INLB") (class "Default")
      (node (ref "J4") (pin "7") (pinfunction "7_7") (pintype "passive"))
      (node (ref "R38") (pin "2") (pinfunction "2_2") (pintype "passive"))
      (node (ref "U1") (pin "40") (pinfunction "INLB_40") (pintype "input"))
    )
    (net (code "18") (name "/INLC") (class "Default")
      (node (ref "J4") (pin "11") (pinfunction "11_11") (pintype "passive"))
      (node (ref "U1") (pin "42") (pinfunction "INLC_42") (pintype "input"))
    )
    (net (code "19") (name "/ISENA") (class "Default")
      (node (ref "C14") (pin "1") (pinfunction "1_1") (pintype "passive"))
      (node (ref "J3") (pin "16") (pinfunction "16_16") (pintype "passive"))
      (node (ref "R18") (pin "1") (pinfunction "1_1") (pintype "passive"))
    )
    (net (code "20") (name "/ISENB") (class "Default")
      (node (ref "C15") (pin "1") (pinfunction "1_1") (pintype "passive"))
      (node (ref "J3") (pin "14") (pinfunction "14_14") (pintype "passive"))
      (node (ref "R20") (pin "1") (pinfunction "1_1") (pintype "passive"))
    )
    (net (code "21") (name "/ISENC") (class "Default")
      (node (ref "C16") (pin "1") (pinfunction "1_1") (pintype "passive"))
      (node (ref "J3") (pin "12") (pinfunction "12_12") (pintype "passive"))
      (node (ref "R21") (pin "1") (pinfunction "1_1") (pintype "passive"))
    )
    (net (code "22") (name "/LED") (class "Default")
      (node (ref "D5") (pin "1") (pinfunction "A_1") (pintype "passive"))
      (node (ref "J4") (pin "15") (pinfunction "15_15") (pintype "passive"))
    )
    (net (code "23") (name "/MODE") (class "Default")
      (node (ref "J4") (pin "13") (pinfunction "13_13") (pintype "passive"))
      (node (ref "R14") (pin "2") (pinfunction "2_2") (pintype "passive"))
      (node (ref "R23") (pin "2") (pinfunction "2_2") (pintype "passive"))
    )
    (net (code "24") (name "/MOTA") (class "Default")
      (node (ref "J5") (pin "1") (pinfunction "1_1") (pintype "passive"))
      (node (ref "R2") (pin "2") (pinfunction "2_2") (pintype "passive"))
      (node (ref "TP4") (pin "1") (pintype "passive"))
      (node (ref "U2") (pin "10") (pinfunction "VSW_10") (pintype "passive"))
      (node (ref "U2") (pin "11") (pinfunction "VSW_11") (pintype "passive"))
      (node (ref "U2") (pin "3") (pinfunction "VSW_3") (pintype "passive"))
      (node (ref "U2") (pin "4") (pinfunction "VSW_4") (pintype "passive"))
      (node (ref "U2") (pin "5") (pinfunction "VSW_5") (pintype "passive"))
      (node (ref "U2") (pin "6") (pinfunction "VSW_6") (pintype "passive"))
      (node (ref "U2") (pin "7") (pinfunction "VSW_7") (pintype "passive"))
      (node (ref "U2") (pin "8") (pinfunction "VSW_8") (pintype "passive"))
      (node (ref "U2") (pin "9") (pinfunction "VSW_9") (pintype "passive"))
    )
    (net (code "25") (name "/MOTB") (class "Default")
      (node (ref "J5") (pin "2") (pinfunction "2_2") (pintype "passive"))
      (node (ref "R3") (pin "2") (pinfunction "2_2") (pintype "passive"))
      (node (ref "TP5") (pin "1") (pintype "passive"))
      (node (ref "U3") (pin "10") (pinfunction "VSW_10") (pintype "passive"))
      (node (ref "U3") (pin "11") (pinfunction "VSW_11") (pintype "passive"))
      (node (ref "U3") (pin "3") (pinfunction "VSW_3") (pintype "passive"))
      (node (ref "U3") (pin "4") (pinfunction "VSW_4") (pintype "passive"))
      (node (ref "U3") (pin "5") (pinfunction "VSW_5") (pintype "passive"))
      (node (ref "U3") (pin "6") (pinfunction "VSW_6") (pintype "passive"))
      (node (ref "U3") (pin "7") (pinfunction "VSW_7") (pintype "passive"))
      (node (ref "U3") (pin "8") (pinfunction "VSW_8") (pintype "passive"))
      (node (ref "U3") (pin "9") (pinfunction "VSW_9") (pintype "passive"))
    )
    (net (code "26") (name "/MOTC") (class "Default")
      (node (ref "J5") (pin "3") (pinfunction "3_3") (pintype "passive"))
      (node (ref "R4") (pin "2") (pinfunction "2_2") (pintype "passive"))
      (node (ref "TP6") (pin "1") (pintype "passive"))
      (node (ref "U4") (pin "10") (pinfunction "VSW_10") (pintype "passive"))
      (node (ref "U4") (pin "11") (pinfunction "VSW_11") (pintype "passive"))
      (node (ref "U4") (pin "3") (pinfunction "VSW_3") (pintype "passive"))
      (node (ref "U4") (pin "4") (pinfunction "VSW_4") (pintype "passive"))
      (node (ref "U4") (pin "5") (pinfunction "VSW_5") (pintype "passive"))
      (node (ref "U4") (pin "6") (pinfunction "VSW_6") (pintype "passive"))
      (node (ref "U4") (pin "7") (pinfunction "VSW_7") (pintype "passive"))
      (node (ref "U4") (pin "8") (pinfunction "VSW_8") (pintype "passive"))
      (node (ref "U4") (pin "9") (pinfunction "VSW_9") (pintype "passive"))
    )
    (net (code "27") (name "/POT") (class "Default")
      (node (ref "J3") (pin "11") (pinfunction "11_11") (pintype "passive"))
      (node (ref "R33") (pin "2") (pinfunction "WIPER_2") (pintype "passive"))
    )
    (net (code "28") (name "/SCLK") (class "Default")
      (node (ref "J3") (pin "13") (pinfunction "13_13") (pintype "passive"))
      (node (ref "R17") (pin "2") (pinfunction "2_2") (pintype "passive"))
    )
    (net (code "29") (name "/SDI") (class "Default")
      (node (ref "J4") (pin "12") (pinfunction "12_12") (pintype "passive"))
      (node (ref "R15") (pin "2") (pinfunction "2_2") (pintype "passive"))
    )
    (net (code "30") (name "/SDO") (class "Default")
      (node (ref "J4") (pin "14") (pinfunction "14_14") (pintype "passive"))
      (node (ref "R13") (pin "2") (pinfunction "2_2") (pintype "passive"))
    )
    (net (code "31") (name "/SHA") (class "Default")
      (node (ref "NT2") (pin "2") (pinfunction "2_2") (pintype "passive"))
      (node (ref "U1") (pin "9") (pinfunction "SHA_9") (pintype "input"))
    )
    (net (code "32") (name "/SHB") (class "Default")
      (node (ref "NT3") (pin "2") (pinfunction "2_2") (pintype "passive"))
      (node (ref "U1") (pin "16") (pinfunction "SHB_16") (pintype "input"))
    )
    (net (code "33") (name "/SHC") (class "Default")
      (node (ref "NT4") (pin "2") (pinfunction "2_2") (pintype "passive"))
      (node (ref "U1") (pin "19") (pinfunction "SHC_19") (pintype "input"))
    )
    (net (code "34") (name "/SLA") (class "Default")
      (node (ref "C1") (pin "2") (pinfunction "2_2") (pintype "passive"))
      (node (ref "NT5") (pin "2") (pinfunction "2_2") (pintype "passive"))
      (node (ref "R6") (pin "2") (pinfunction "2_2") (pintype "passive"))
      (node (ref "U2") (pin "12") (pinfunction "PGND_12") (pintype "power_in"))
      (node (ref "U2") (pin "13") (pinfunction "PGND_13") (pintype "power_in"))
      (node (ref "U2") (pin "14") (pinfunction "PGND_14") (pintype "power_in"))
      (node (ref "U2") (pin "15") (pinfunction "PGND_15") (pintype "power_in"))
      (node (ref "U2") (pin "16") (pinfunction "PGND_16") (pintype "power_in"))
      (node (ref "U2") (pin "17") (pinfunction "PGND_17") (pintype "power_in"))
      (node (ref "U2") (pin "18") (pinfunction "PGND_18") (pintype "power_in"))
      (node (ref "U2") (pin "19") (pinfunction "PGND_19") (pintype "power_in"))
      (node (ref "U2") (pin "20") (pinfunction "PGND_20") (pintype "power_in"))
    )
    (net (code "35") (name "/SLB") (class "Default")
      (node (ref "C2") (pin "2") (pinfunction "2_2") (pintype "passive"))
      (node (ref "NT6") (pin "2") (pinfunction "2_2") (pintype "passive"))
      (node (ref "R8") (pin "2") (pinfunction "2_2") (pintype "passive"))
      (node (ref "U3") (pin "12") (pinfunction "PGND_12") (pintype "power_in"))
      (node (ref "U3") (pin "13") (pinfunction "PGND_13") (pintype "power_in"))
      (node (ref "U3") (pin "14") (pinfunction "PGND_14") (pintype "power_in"))
      (node (ref "U3") (pin "15") (pinfunction "PGND_15") (pintype "power_in"))
      (node (ref "U3") (pin "16") (pinfunction "PGND_16") (pintype "power_in"))
      (node (ref "U3") (pin "17") (pinfunction "PGND_17") (pintype "power_in"))
      (node (ref "U3") (pin "18") (pinfunction "PGND_18") (pintype "power_in"))
      (node (ref "U3") (pin "19") (pinfunction "PGND_19") (pintype "power_in"))
      (node (ref "U3") (pin "20") (pinfunction "PGND_20") (pintype "power_in"))
    )
    (net (code "36") (name "/SLC") (class "Default")
      (node (ref "C3") (pin "2") (pinfunction "2_2") (pintype "passive"))
      (node (ref "NT7") (pin "2") (pinfunction "2_2") (pintype "passive"))
      (node (ref "R10") (pin "2") (pinfunction "2_2") (pintype "passive"))
      (node (ref "U4") (pin "12") (pinfunction "PGND_12") (pintype "power_in"))
      (node (ref "U4") (pin "13") (pinfunction "PGND_13") (pintype "power_in"))
      (node (ref "U4") (pin "14") (pinfunction "PGND_14") (pintype "power_in"))
      (node (ref "U4") (pin "15") (pinfunction "PGND_15") (pintype "power_in"))
      (node (ref "U4") (pin "16") (pinfunction "PGND_16") (pintype "power_in"))
      (node (ref "U4") (pin "17") (pinfunction "PGND_17") (pintype "power_in"))
      (node (ref "U4") (pin "18") (pinfunction "PGND_18") (pintype "power_in"))
      (node (ref "U4") (pin "19") (pinfunction "PGND_19") (pintype "power_in"))
      (node (ref "U4") (pin "20") (pinfunction "PGND_20") (pintype "power_in"))
    )
    (net (code "37") (name "/SNA") (class "Default")
      (node (ref "C17") (pin "2") (pinfunction "2_2") (pintype "passive"))
      (node (ref "NT8") (pin "1") (pinfunction "1_1") (pintype "passive"))
      (node (ref "U1") (pin "12") (pinfunction "SNA_12") (pintype "input"))
    )
    (net (code "38") (name "/SNB") (class "Default")
      (node (ref "C13") (pin "2") (pinfunction "2_2") (pintype "passive"))
      (node (ref "NT9") (pin "1") (pinfunction "1_1") (pintype "passive"))
      (node (ref "U1") (pin "13") (pinfunction "SNB_13") (pintype "input"))
    )
    (net (code "39") (name "/SNC") (class "Default")
      (node (ref "C12") (pin "2") (pinfunction "2_2") (pintype "passive"))
      (node (ref "NT10") (pin "1") (pinfunction "1_1") (pintype "passive"))
      (node (ref "U1") (pin "22") (pinfunction "SNC_22") (pintype "input"))
    )
    (net (code "40") (name "/SOA") (class "Default")
      (node (ref "R18") (pin "2") (pinfunction "2_2") (pintype "passive"))
      (node (ref "U1") (pin "25") (pinfunction "SOA_25") (pintype "output"))
    )
    (net (code "41") (name "/SOB") (class "Default")
      (node (ref "R20") (pin "2") (pinfunction "2_2") (pintype "passive"))
      (node (ref "U1") (pin "24") (pinfunction "SOB_24") (pintype "output"))
    )
    (net (code "42") (name "/SOC") (class "Default")
      (node (ref "R21") (pin "2") (pinfunction "2_2") (pintype "passive"))
      (node (ref "U1") (pin "23") (pinfunction "SOC_23") (pintype "output"))
    )
    (net (code "43") (name "/SPA") (class "Default")
      (node (ref "C17") (pin "1") (pinfunction "1_1") (pintype "passive"))
      (node (ref "NT5") (pin "1") (pinfunction "1_1") (pintype "passive"))
      (node (ref "U1") (pin "11") (pinfunction "SPA_11") (pintype "input"))
    )
    (net (code "44") (name "/SPB") (class "Default")
      (node (ref "C13") (pin "1") (pinfunction "1_1") (pintype "passive"))
      (node (ref "NT6") (pin "1") (pinfunction "1_1") (pintype "passive"))
      (node (ref "U1") (pin "14") (pinfunction "SPB_14") (pintype "input"))
    )
    (net (code "45") (name "/SPC") (class "Default")
      (node (ref "C12") (pin "1") (pinfunction "1_1") (pintype "passive"))
      (node (ref "NT7") (pin "1") (pinfunction "1_1") (pintype "passive"))
      (node (ref "U1") (pin "21") (pinfunction "SPC_21") (pintype "input"))
    )
    (net (code "46") (name "/VDRAIN") (class "Default")
      (node (ref "NT1") (pin "1") (pinfunction "1_1") (pintype "passive"))
      (node (ref "U1") (pin "7") (pinfunction "VDRAIN_7") (pintype "input"))
    )
    (net (code "47") (name "/VDS") (class "Default")
      (node (ref "J3") (pin "20") (pinfunction "20_20") (pintype "passive"))
      (node (ref "R16") (pin "1") (pinfunction "1_1") (pintype "passive"))
      (node (ref "R17") (pin "1") (pinfunction "1_1") (pintype "passive"))
      (node (ref "R19") (pin "2") (pinfunction "2_2") (pintype "passive"))
      (node (ref "U1") (pin "31") (pinfunction "SCLK_31") (pintype "input"))
    )
    (net (code "48") (name "/VSENA") (class "Default")
      (node (ref "C9") (pin "1") (pinfunction "1_1") (pintype "passive"))
      (node (ref "D1") (pin "1") (pinfunction "D1+_1") (pintype "passive"))
      (node (ref "J3") (pin "6") (pinfunction "6_6") (pintype "passive"))
      (node (ref "R2") (pin "1") (pinfunction "1_1") (pintype "passive"))
      (node (ref "R7") (pin "2") (pinfunction "2_2") (pintype "passive"))
    )
    (net (code "49") (name "/VSENB") (class "Default")
      (node (ref "C10") (pin "1") (pinfunction "1_1") (pintype "passive"))
      (node (ref "D1") (pin "3") (pinfunction "D2+_3") (pintype "passive"))
      (node (ref "J3") (pin "8") (pinfunction "8_8") (pintype "passive"))
      (node (ref "R3") (pin "1") (pinfunction "1_1") (pintype "passive"))
      (node (ref "R9") (pin "2") (pinfunction "2_2") (pintype "passive"))
    )
    (net (code "50") (name "/VSENC") (class "Default")
      (node (ref "C11") (pin "1") (pinfunction "1_1") (pintype "passive"))
      (node (ref "D1") (pin "4") (pinfunction "D2-_4") (pintype "passive"))
      (node (ref "J3") (pin "10") (pinfunction "10_10") (pintype "passive"))
      (node (ref "R11") (pin "2") (pinfunction "2_2") (pintype "passive"))
      (node (ref "R4") (pin "1") (pinfunction "1_1") (pintype "passive"))
    )
    (net (code "51") (name "/VSENVM") (class "Default")
      (node (ref "C24") (pin "1") (pinfunction "1_1") (pintype "passive"))
      (node (ref "D1") (pin "6") (pinfunction "D1-_6") (pintype "passive"))
      (node (ref "J3") (pin "3") (pinfunction "3_3") (pintype "passive"))
      (node (ref "R28") (pin "1") (pinfunction "1_1") (pintype "passive"))
      (node (ref "R32") (pin "2") (pinfunction "2_2") (pintype "passive"))
    )
    (net (code "52") (name "/nFAULT") (class "Default")
      (node (ref "J3") (pin "15") (pinfunction "15_15") (pintype "passive"))
      (node (ref "R24") (pin "1") (pinfunction "1_1") (pintype "passive"))
      (node (ref "R25") (pin "1") (pinfunction "1_1") (pintype "passive"))
      (node (ref "U1") (pin "28") (pinfunction "FAULT_28") (pintype "open_collector"))
    )
    (net (code "53") (name "/nSCS{slash}GAIN") (class "Default")
      (node (ref "J4") (pin "18") (pinfunction "18_18") (pintype "passive"))
      (node (ref "R22") (pin "2") (pinfunction "2_2") (pintype "passive"))
      (node (ref "U1") (pin "32") (pinfunction "SCS_32") (pintype "input"))
    )
    (net (code "54") (name "3.3V") (class "Default")
      (node (ref "C18") (pin "1") (pinfunction "1_1") (pintype "passive"))
      (node (ref "C21") (pin "1") (pinfunction "1_1") (pintype "passive"))
      (node (ref "D1") (pin "5") (pinfunction "VCC_5") (pintype "power_in"))
      (node (ref "D2") (pin "1") (pinfunction "A_1") (pintype "passive"))
      (node (ref "D4") (pin "1") (pinfunction "A_1") (pintype "passive"))
      (node (ref "J2") (pin "5") (pinfunction "5_5") (pintype "passive"))
      (node (ref "J3") (pin "1") (pinfunction "1_1") (pintype "passive"))
      (node (ref "L1") (pin "2") (pinfunction "2_2") (pintype "passive"))
      (node (ref "R1") (pin "2") (pinfunction "2_2") (pintype "passive"))
      (node (ref "R12") (pin "2") (pinfunction "2_2") (pintype "passive"))
      (node (ref "R16") (pin "2") (pinfunction "2_2") (pintype "passive"))
      (node (ref "R25") (pin "2") (pinfunction "2_2") (pintype "passive"))
      (node (ref "R26") (pin "2") (pinfunction "2_2") (pintype "passive"))
      (node (ref "R29") (pin "2") (pinfunction "2_2") (pintype "passive"))
      (node (ref "R30") (pin "2") (pinfunction "2_2") (pintype "passive"))
      (node (ref "R31") (pin "2") (pinfunction "2_2") (pintype "passive"))
      (node (ref "R33") (pin "3") (pinfunction "CW_3") (pintype "passive"))
      (node (ref "R39") (pin "2") (pinfunction "2_2") (pintype "passive"))
      (node (ref "R40") (pin "2") (pinfunction "2_2") (pintype "passive"))
      (node (ref "U1") (pin "26") (pinfunction "VREF_26") (pintype "input"))
    )
    (net (code "55") (name "GND") (class "Default")
      (node (ref "C10") (pin "2") (pinfunction "2_2") (pintype "passive"))
      (node (ref "C11") (pin "2") (pinfunction "2_2") (pintype "passive"))
      (node (ref "C14") (pin "2") (pinfunction "2_2") (pintype "passive"))
      (node (ref "C15") (pin "2") (pinfunction "2_2") (pintype "passive"))
      (node (ref "C16") (pin "2") (pinfunction "2_2") (pintype "passive"))
      (node (ref "C18") (pin "2") (pinfunction "2_2") (pintype "passive"))
      (node (ref "C20") (pin "2") (pinfunction "2_2") (pintype "passive"))
      (node (ref "C21") (pin "2") (pinfunction "2_2") (pintype "passive"))
      (node (ref "C22") (pin "2") (pinfunction "-_2") (pintype "passive"))
      (node (ref "C23") (pin "2") (pinfunction "-_2") (pintype "passive"))
      (node (ref "C24") (pin "2") (pinfunction "2_2") (pintype "passive"))
      (node (ref "C25") (pin "2") (pinfunction "2_2") (pintype "passive"))
      (node (ref "C26") (pin "2") (pinfunction "2_2") (pintype "passive"))
      (node (ref "C27") (pin "2") (pinfunction "2_2") (pintype "passive"))
      (node (ref "C5") (pin "2") (pinfunction "2_2") (pintype "passive"))
      (node (ref "C6") (pin "2") (pinfunction "2_2") (pintype "passive"))
      (node (ref "C8") (pin "2") (pinfunction "2_2") (pintype "passive"))
      (node (ref "C9") (pin "2") (pinfunction "2_2") (pintype "passive"))
      (node (ref "D1") (pin "2") (pinfunction "GND_2") (pintype "power_in"))
      (node (ref "D3") (pin "2") (pinfunction "A_2") (pintype "passive"))
      (node (ref "J1") (pin "2") (pinfunction "2_2") (pintype "passive"))
      (node (ref "J2") (pin "1") (pinfunction "1_1") (pintype "passive"))
      (node (ref "J3") (pin "4") (pinfunction "4_4") (pintype "passive"))
      (node (ref "J4") (pin "2") (pinfunction "2_2") (pintype "passive"))
      (node (ref "NT10") (pin "2") (pinfunction "2_2") (pintype "passive"))
      (node (ref "NT8") (pin "2") (pinfunction "2_2") (pintype "passive"))
      (node (ref "NT9") (pin "2") (pinfunction "2_2") (pintype "passive"))
      (node (ref "R10") (pin "1") (pinfunction "1_1") (pintype "passive"))
      (node (ref "R11") (pin "1") (pinfunction "1_1") (pintype "passive"))
      (node (ref "R19") (pin "1") (pinfunction "1_1") (pintype "passive"))
      (node (ref "R22") (pin "1") (pinfunction "1_1") (pintype "passive"))
      (node (ref "R23") (pin "1") (pinfunction "1_1") (pintype "passive"))
      (node (ref "R27") (pin "1") (pinfunction "1_1") (pintype "passive"))
      (node (ref "R32") (pin "1") (pinfunction "1_1") (pintype "passive"))
      (node (ref "R33") (pin "1") (pinfunction "CCW_1") (pintype "passive"))
      (node (ref "R34") (pin "1") (pinfunction "1_1") (pintype "passive"))
      (node (ref "R35") (pin "1") (pinfunction "1_1") (pintype "passive"))
      (node (ref "R41") (pin "1") (pinfunction "1_1") (pintype "passive"))
      (node (ref "R42") (pin "1") (pinfunction "1_1") (pintype "passive"))
      (node (ref "R5") (pin "1") (pinfunction "1_1") (pintype "passive"))
      (node (ref "R6") (pin "1") (pinfunction "1_1") (pintype "passive"))
      (node (ref "R7") (pin "1") (pinfunction "1_1") (pintype "passive"))
      (node (ref "R8") (pin "1") (pinfunction "1_1") (pintype "passive"))
      (node (ref "R9") (pin "1") (pinfunction "1_1") (pintype "passive"))
      (node (ref "TP10") (pin "1") (pinfunction "1_1") (pintype "passive"))
      (node (ref "TP10") (pin "2") (pinfunction "2_2") (pintype "passive"))
      (node (ref "U1") (pin "2") (pinfunction "PGND_2") (pintype "power_in"))
      (node (ref "U1") (pin "27") (pinfunction "DGND_27") (pintype "power_in"))
      (node (ref "U1") (pin "35") (pinfunction "AGND_35") (pintype "power_in"))
      (node (ref "U1") (pin "43") (pinfunction "BGND_43") (pintype "power_in"))
      (node (ref "U1") (pin "46") (pinfunction "BGND_46") (pintype "power_in"))
      (node (ref "U1") (pin "49") (pinfunction "PAD_49") (pintype "power_in"))
    )
    (net (code "56") (name "Net-(D2-K)") (class "Default")
      (node (ref "D2") (pin "2") (pinfunction "K_2") (pintype "passive"))
      (node (ref "R24") (pin "2") (pinfunction "2_2") (pintype "passive"))
    )
    (net (code "57") (name "Net-(D3-K)") (class "Default")
      (node (ref "C19") (pin "2") (pinfunction "2_2") (pintype "passive"))
      (node (ref "D3") (pin "1") (pinfunction "K_1") (pintype "passive"))
      (node (ref "L1") (pin "1") (pinfunction "1_1") (pintype "passive"))
      (node (ref "U1") (pin "45") (pinfunction "SW_45") (pintype "power_in"))
    )
    (net (code "58") (name "Net-(D4-K)") (class "Default")
      (node (ref "D4") (pin "2") (pinfunction "K_2") (pintype "passive"))
      (node (ref "R34") (pin "2") (pinfunction "2_2") (pintype "passive"))
    )
    (net (code "59") (name "Net-(D5-K)") (class "Default")
      (node (ref "D5") (pin "2") (pinfunction "K_2") (pintype "passive"))
      (node (ref "R35") (pin "2") (pinfunction "2_2") (pintype "passive"))
    )
    (net (code "60") (name "Net-(J4-Pad17)") (class "Default")
      (node (ref "J4") (pin "17") (pinfunction "17_17") (pintype "passive"))
      (node (ref "R39") (pin "1") (pinfunction "1_1") (pintype "passive"))
      (node (ref "R41") (pin "2") (pinfunction "2_2") (pintype "passive"))
    )
    (net (code "61") (name "Net-(J4-Pad19)") (class "Default")
      (node (ref "J4") (pin "19") (pinfunction "19_19") (pintype "passive"))
      (node (ref "R40") (pin "1") (pinfunction "1_1") (pintype "passive"))
      (node (ref "R42") (pin "2") (pinfunction "2_2") (pintype "passive"))
    )
    (net (code "62") (name "Net-(U1-CB)") (class "Default")
      (node (ref "C19") (pin "1") (pinfunction "1_1") (pintype "passive"))
      (node (ref "U1") (pin "44") (pinfunction "CB_44") (pintype "power_in"))
    )
    (net (code "63") (name "Net-(U1-CPH)") (class "Default")
      (node (ref "C7") (pin "1") (pinfunction "1_1") (pintype "passive"))
      (node (ref "U1") (pin "4") (pinfunction "CPH_4") (pintype "passive"))
    )
    (net (code "64") (name "Net-(U1-CPL)") (class "Default")
      (node (ref "C7") (pin "2") (pinfunction "2_2") (pintype "passive"))
      (node (ref "U1") (pin "3") (pinfunction "CPL_3") (pintype "passive"))
    )
    (net (code "65") (name "Net-(U1-DVDD)") (class "Default")
      (node (ref "C8") (pin "1") (pinfunction "1_1") (pintype "passive"))
      (node (ref "U1") (pin "36") (pinfunction "DVDD_36") (pintype "power_in"))
    )
    (net (code "66") (name "Net-(U1-FB)") (class "Default")
      (node (ref "R26") (pin "1") (pinfunction "1_1") (pintype "passive"))
      (node (ref "R27") (pin "2") (pinfunction "2_2") (pintype "passive"))
      (node (ref "U1") (pin "1") (pinfunction "FB_1") (pintype "input"))
    )
    (net (code "67") (name "Net-(U1-SDO)") (class "Default")
      (node (ref "R12") (pin "1") (pinfunction "1_1") (pintype "passive"))
      (node (ref "R13") (pin "1") (pinfunction "1_1") (pintype "passive"))
      (node (ref "R14") (pin "1") (pinfunction "1_1") (pintype "passive"))
      (node (ref "U1") (pin "29") (pinfunction "SDO_29") (pintype "passive"))
    )
    (net (code "68") (name "Net-(U1-VCP)") (class "Default")
      (node (ref "C4") (pin "2") (pinfunction "2_2") (pintype "passive"))
      (node (ref "U1") (pin "5") (pinfunction "VCP_5") (pintype "power_in"))
    )
    (net (code "69") (name "Net-(U2-SH)") (class "Default")
      (node (ref "NT2") (pin "1") (pinfunction "1_1") (pintype "passive"))
      (node (ref "U2") (pin "2") (pinfunction "SH_2") (pintype "passive"))
    )
    (net (code "70") (name "Net-(U3-SH)") (class "Default")
      (node (ref "NT3") (pin "1") (pinfunction "1_1") (pintype "passive"))
      (node (ref "U3") (pin "2") (pinfunction "SH_2") (pintype "passive"))
    )
    (net (code "71") (name "Net-(U4-SH)") (class "Default")
      (node (ref "NT4") (pin "1") (pinfunction "1_1") (pintype "passive"))
      (node (ref "U4") (pin "2") (pinfunction "SH_2") (pintype "passive"))
    )
    (net (code "72") (name "VM") (class "Default")
      (node (ref "C1") (pin "1") (pinfunction "1_1") (pintype "passive"))
      (node (ref "C2") (pin "1") (pinfunction "1_1") (pintype "passive"))
      (node (ref "C20") (pin "1") (pinfunction "1_1") (pintype "passive"))
      (node (ref "C22") (pin "1") (pinfunction "+_1") (pintype "passive"))
      (node (ref "C23") (pin "1") (pinfunction "+_1") (pintype "passive"))
      (node (ref "C3") (pin "1") (pinfunction "1_1") (pintype "passive"))
      (node (ref "C4") (pin "1") (pinfunction "1_1") (pintype "passive"))
      (node (ref "C5") (pin "1") (pinfunction "1_1") (pintype "passive"))
      (node (ref "C6") (pin "1") (pinfunction "1_1") (pintype "passive"))
      (node (ref "J1") (pin "1") (pinfunction "1_1") (pintype "passive"))
      (node (ref "NT1") (pin "2") (pinfunction "2_2") (pintype "passive"))
      (node (ref "R28") (pin "2") (pinfunction "2_2") (pintype "passive"))
      (node (ref "U1") (pin "47") (pinfunction "VIN_47") (pintype "power_in"))
      (node (ref "U1") (pin "48") (pinfunction "SHDN_48") (pintype "input"))
      (node (ref "U1") (pin "6") (pinfunction "VM_6") (pintype "power_in"))
      (node (ref "U2") (pin "27") (pinfunction "VIN_27") (pintype "power_in"))
      (node (ref "U3") (pin "27") (pinfunction "VIN_27") (pintype "power_in"))
      (node (ref "U4") (pin "27") (pinfunction "VIN_27") (pintype "power_in"))
    )
    (net (code "73") (name "unconnected-(J3-Pad2)") (class "Default")
      (node (ref "J3") (pin "2") (pinfunction "2_2") (pintype "passive+no_connect"))
    )
    (net (code "74") (name "unconnected-(J3-Pad5)") (class "Default")
      (node (ref "J3") (pin "5") (pinfunction "5_5") (pintype "passive+no_connect"))
    )
    (net (code "75") (name "unconnected-(J3-Pad7)") (class "Default")
      (node (ref "J3") (pin "7") (pinfunction "7_7") (pintype "passive+no_connect"))
    )
    (net (code "76") (name "unconnected-(J3-Pad17)") (class "Default")
      (node (ref "J3") (pin "17") (pinfunction "17_17") (pintype "passive+no_connect"))
    )
    (net (code "77") (name "unconnected-(J3-Pad19)") (class "Default")
      (node (ref "J3") (pin "19") (pinfunction "19_19") (pintype "passive+no_connect"))
    )
    (net (code "78") (name "unconnected-(J4-Pad8)") (class "Default")
      (node (ref "J4") (pin "8") (pinfunction "8_8") (pintype "passive+no_connect"))
    )
    (net (code "79") (name "unconnected-(J4-Pad10)") (class "Default")
      (node (ref "J4") (pin "10") (pinfunction "10_10") (pintype "passive+no_connect"))
    )
    (net (code "80") (name "unconnected-(U2-NC-Pad21)") (class "Default")
      (node (ref "U2") (pin "21") (pinfunction "NC_21") (pintype "passive+no_connect"))
    )
    (net (code "81") (name "unconnected-(U2-NC-Pad23)") (class "Default")
      (node (ref "U2") (pin "23") (pinfunction "NC_23") (pintype "passive+no_connect"))
    )
    (net (code "82") (name "unconnected-(U2-NC-Pad24)") (class "Default")
      (node (ref "U2") (pin "24") (pinfunction "NC_24") (pintype "passive+no_connect"))
    )
    (net (code "83") (name "unconnected-(U2-NC-Pad25)") (class "Default")
      (node (ref "U2") (pin "25") (pinfunction "NC_25") (pintype "passive+no_connect"))
    )
    (net (code "84") (name "unconnected-(U2-NC-Pad26)") (class "Default")
      (node (ref "U2") (pin "26") (pinfunction "NC_26") (pintype "passive+no_connect"))
    )
    (net (code "85") (name "unconnected-(U3-NC-Pad21)") (class "Default")
      (node (ref "U3") (pin "21") (pinfunction "NC_21") (pintype "passive+no_connect"))
    )
    (net (code "86") (name "unconnected-(U3-NC-Pad23)") (class "Default")
      (node (ref "U3") (pin "23") (pinfunction "NC_23") (pintype "passive+no_connect"))
    )
    (net (code "87") (name "unconnected-(U3-NC-Pad24)") (class "Default")
      (node (ref "U3") (pin "24") (pinfunction "NC_24") (pintype "passive+no_connect"))
    )
    (net (code "88") (name "unconnected-(U3-NC-Pad25)") (class "Default")
      (node (ref "U3") (pin "25") (pinfunction "NC_25") (pintype "passive+no_connect"))
    )
    (net (code "89") (name "unconnected-(U3-NC-Pad26)") (class "Default")
      (node (ref "U3") (pin "26") (pinfunction "NC_26") (pintype "passive+no_connect"))
    )
    (net (code "90") (name "unconnected-(U4-NC-Pad21)") (class "Default")
      (node (ref "U4") (pin "21") (pinfunction "NC_21") (pintype "passive+no_connect"))
    )
    (net (code "91") (name "unconnected-(U4-NC-Pad23)") (class "Default")
      (node (ref "U4") (pin "23") (pinfunction "NC_23") (pintype "passive+no_connect"))
    )
    (net (code "92") (name "unconnected-(U4-NC-Pad24)") (class "Default")
      (node (ref "U4") (pin "24") (pinfunction "NC_24") (pintype "passive+no_connect"))
    )
    (net (code "93") (name "unconnected-(U4-NC-Pad25)") (class "Default")
      (node (ref "U4") (pin "25") (pinfunction "NC_25") (pintype "passive+no_connect"))
    )
    (net (code "94") (name "unconnected-(U4-NC-Pad26)") (class "Default")
      (node (ref "U4") (pin "26") (pinfunction "NC_26") (pintype "passive+no_connect"))
    )
  )
)
